# es.net
KiCad netlist of a schematic drawn in EAGLE
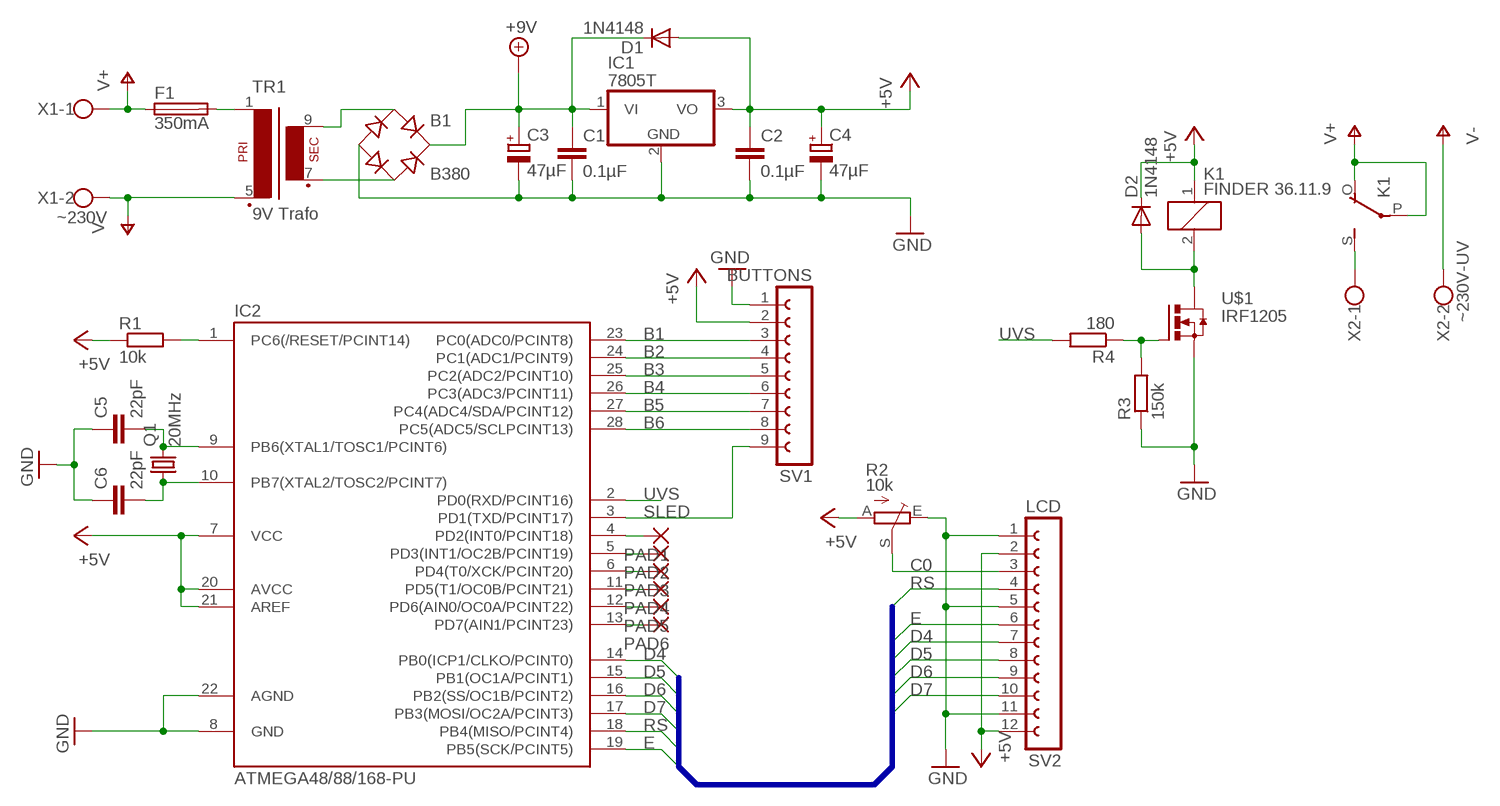
[diagram p0: schematic, sheet 1]

(export (version "E")
  (design (tool "Eeschema 10.0.6"))
  (components
    (comp (ref "B1")
      (value "B380")
      (footprint "eagle-import:RB1A")
      (libsource (lib "eagle-import") (part "RB1A"))
    )
    (comp (ref "C1")
      (value "0.1µF")
      (footprint "eagle-import:C025-024X044")
      (libsource (lib "eagle-import") (part "C-EU025-024X044"))
    )
    (comp (ref "C2")
      (value "0.1µF")
      (footprint "eagle-import:C025-024X044")
      (libsource (lib "eagle-import") (part "C-EU025-024X044"))
    )
    (comp (ref "C3")
      (value "47µF")
      (footprint "eagle-import:E2,5-5")
      (libsource (lib "eagle-import") (part "CPOL-EUE2.5-5"))
    )
    (comp (ref "C4")
      (value "47µF")
      (footprint "eagle-import:E2,5-5")
      (libsource (lib "eagle-import") (part "CPOL-EUE2.5-5"))
    )
    (comp (ref "C5")
      (value "22pF")
      (footprint "eagle-import:C050-024X044")
      (libsource (lib "eagle-import") (part "C-EU050-024X044"))
    )
    (comp (ref "C6")
      (value "22pF")
      (footprint "eagle-import:C050-024X044")
      (libsource (lib "eagle-import") (part "C-EU050-024X044"))
    )
    (comp (ref "D1")
      (value "1N4148")
      (footprint "eagle-import:DO35-7")
      (libsource (lib "eagle-import") (part "1N4148DO35-7"))
    )
    (comp (ref "D2")
      (value "1N4148")
      (footprint "eagle-import:DO35-7")
      (libsource (lib "eagle-import") (part "1N4148DO35-7"))
    )
    (comp (ref "F1")
      (value "350mA")
      (footprint "eagle-import:SHK20Q")
      (libsource (lib "eagle-import") (part "FUSESHK20Q"))
    )
    (comp (ref "IC1")
      (value "7805T")
      (footprint "eagle-import:TO220H")
      (libsource (lib "eagle-import") (part "78T05"))
    )
    (comp (ref "IC2")
      (value "ATMEGA48/88/168-PU")
      (footprint "eagle-import:DIL28-3")
      (libsource (lib "eagle-import") (part "ATMEGA48/88/168-PU"))
    )
    (comp (ref "K1")
      (value "FINDER 36.11.9")
      (footprint "eagle-import:G5LE")
      (libsource (lib "eagle-import") (part "G5LE"))
    )
    (comp (ref "PAD1")
      (value "1,6/0,8")
      (footprint "eagle-import:1,6_0,8")
      (libsource (lib "eagle-import") (part "1,6/0,8"))
    )
    (comp (ref "PAD2")
      (value "1,6/0,8")
      (footprint "eagle-import:1,6_0,8")
      (libsource (lib "eagle-import") (part "1,6/0,8"))
    )
    (comp (ref "PAD3")
      (value "1,6/0,8")
      (footprint "eagle-import:1,6_0,8")
      (libsource (lib "eagle-import") (part "1,6/0,8"))
    )
    (comp (ref "PAD4")
      (value "1,6/0,8")
      (footprint "eagle-import:1,6_0,8")
      (libsource (lib "eagle-import") (part "1,6/0,8"))
    )
    (comp (ref "PAD5")
      (value "1,6/0,8")
      (footprint "eagle-import:1,6_0,8")
      (libsource (lib "eagle-import") (part "1,6/0,8"))
    )
    (comp (ref "PAD6")
      (value "1,6/0,8")
      (footprint "eagle-import:1,6_0,8")
      (libsource (lib "eagle-import") (part "1,6/0,8"))
    )
    (comp (ref "Q1")
      (value "20MHz")
      (footprint "eagle-import:HC49_S")
      (libsource (lib "eagle-import") (part "CRYSTALHC49S"))
    )
    (comp (ref "R1")
      (value "10k")
      (footprint "eagle-import:0204_7")
      (libsource (lib "eagle-import") (part "R-EU_0204/7"))
    )
    (comp (ref "R2")
      (value "10k")
      (footprint "eagle-import:LI15")
      (libsource (lib "eagle-import") (part "TRIM_EU-LI15"))
    )
    (comp (ref "R3")
      (value "150k")
      (footprint "eagle-import:0204_7")
      (libsource (lib "eagle-import") (part "R-EU_0204/7"))
    )
    (comp (ref "R4")
      (value "180")
      (footprint "eagle-import:0204_7")
      (libsource (lib "eagle-import") (part "R-EU_0204/7"))
    )
    (comp (ref "SV1")
      (value "BUTTONS")
      (footprint "eagle-import:FE09")
      (libsource (lib "eagle-import") (part "FE09-1"))
    )
    (comp (ref "SV2")
      (value "LCD")
      (footprint "eagle-import:FE12")
      (libsource (lib "eagle-import") (part "FE12-1"))
    )
    (comp (ref "TR1")
      (value "9V Trafo")
      (footprint "eagle-import:EI42-1")
      (libsource (lib "eagle-import") (part "EI42-1"))
    )
    (comp (ref "U$1")
      (value "IRF1205")
      (footprint "eagle-import:I-PAK_TO251AA")
      (libsource (lib "eagle-import") (part "IRF1205"))
    )
    (comp (ref "X1")
      (value "~230V")
      (footprint "eagle-import:W237-2N")
      (libsource (lib "eagle-import") (part "W237-2N"))
    )
    (comp (ref "X2")
      (value "~230V-UV")
      (footprint "eagle-import:W237-2N")
      (libsource (lib "eagle-import") (part "W237-2N"))
    )
  )
  (nets
    (net (code "1") (name "+5V") (class "Default")
      (node (ref "C2") (pin "1") (pinfunction "1_1") (pintype "passive"))
      (node (ref "C4") (pin "+") (pinfunction "+_+") (pintype "passive"))
      (node (ref "D1") (pin "A") (pinfunction "A_A") (pintype "passive"))
      (node (ref "D2") (pin "C") (pinfunction "C_C") (pintype "passive"))
      (node (ref "IC1") (pin "3") (pinfunction "VO_3") (pintype "passive"))
      (node (ref "IC2") (pin "20") (pinfunction "AVCC_20") (pintype "passive"))
      (node (ref "IC2") (pin "21") (pinfunction "AREF_21") (pintype "passive"))
      (node (ref "IC2") (pin "7") (pinfunction "VCC_7") (pintype "power_in"))
      (node (ref "K1") (pin "1") (pinfunction "1_1") (pintype "passive"))
      (node (ref "R1") (pin "1") (pinfunction "1_1") (pintype "passive"))
      (node (ref "R2") (pin "A") (pinfunction "A_A") (pintype "passive"))
      (node (ref "SV1") (pin "2") (pinfunction "2_2") (pintype "passive"))
      (node (ref "SV2") (pin "12") (pinfunction "12_12") (pintype "passive"))
      (node (ref "SV2") (pin "2") (pinfunction "2_2") (pintype "passive"))
    )
    (net (code "2") (name "+9V") (class "Default")
      (node (ref "B1") (pin "+") (pinfunction "+_+") (pintype "passive"))
      (node (ref "C1") (pin "1") (pinfunction "1_1") (pintype "passive"))
      (node (ref "C3") (pin "+") (pinfunction "+_+") (pintype "passive"))
      (node (ref "D1") (pin "C") (pinfunction "C_C") (pintype "passive"))
      (node (ref "IC1") (pin "1") (pinfunction "VI_1") (pintype "input"))
    )
    (net (code "3") (name "/B1") (class "Default")
      (node (ref "IC2") (pin "23") (pinfunction "PC0(ADC0/PCINT8)_23") (pintype "bidirectional"))
      (node (ref "SV1") (pin "3") (pinfunction "3_3") (pintype "passive"))
    )
    (net (code "4") (name "/B2") (class "Default")
      (node (ref "IC2") (pin "24") (pinfunction "PC1(ADC1/PCINT9)_24") (pintype "bidirectional"))
      (node (ref "SV1") (pin "4") (pinfunction "4_4") (pintype "passive"))
    )
    (net (code "5") (name "/B3") (class "Default")
      (node (ref "IC2") (pin "25") (pinfunction "PC2(ADC2/PCINT10)_25") (pintype "bidirectional"))
      (node (ref "SV1") (pin "5") (pinfunction "5_5") (pintype "passive"))
    )
    (net (code "6") (name "/B4") (class "Default")
      (node (ref "IC2") (pin "26") (pinfunction "PC3(ADC3/PCINT11)_26") (pintype "bidirectional"))
      (node (ref "SV1") (pin "6") (pinfunction "6_6") (pintype "passive"))
    )
    (net (code "7") (name "/B5") (class "Default")
      (node (ref "IC2") (pin "27") (pinfunction "PC4(ADC4/SDA/PCINT12)_27") (pintype "bidirectional"))
      (node (ref "SV1") (pin "7") (pinfunction "7_7") (pintype "passive"))
    )
    (net (code "8") (name "/B6") (class "Default")
      (node (ref "IC2") (pin "28") (pinfunction "PC5(ADC5/SCLPCINT13)_28") (pintype "bidirectional"))
      (node (ref "SV1") (pin "8") (pinfunction "8_8") (pintype "passive"))
    )
    (net (code "9") (name "/C0") (class "Default")
      (node (ref "R2") (pin "S") (pinfunction "S_S") (pintype "passive"))
      (node (ref "SV2") (pin "3") (pinfunction "3_3") (pintype "passive"))
    )
    (net (code "10") (name "/D4") (class "Default")
      (node (ref "IC2") (pin "14") (pinfunction "PB0(ICP1/CLKO/PCINT0)_14") (pintype "bidirectional"))
      (node (ref "SV2") (pin "7") (pinfunction "7_7") (pintype "passive"))
    )
    (net (code "11") (name "/D5") (class "Default")
      (node (ref "IC2") (pin "15") (pinfunction "PB1(OC1A/PCINT1)_15") (pintype "bidirectional"))
      (node (ref "SV2") (pin "8") (pinfunction "8_8") (pintype "passive"))
    )
    (net (code "12") (name "/D6") (class "Default")
      (node (ref "IC2") (pin "16") (pinfunction "PB2(SS/OC1B/PCINT2)_16") (pintype "bidirectional"))
      (node (ref "SV2") (pin "9") (pinfunction "9_9") (pintype "passive"))
    )
    (net (code "13") (name "/D7") (class "Default")
      (node (ref "IC2") (pin "17") (pinfunction "PB3(MOSI/OC2A/PCINT3)_17") (pintype "bidirectional"))
      (node (ref "SV2") (pin "10") (pinfunction "10_10") (pintype "passive"))
    )
    (net (code "14") (name "/E") (class "Default")
      (node (ref "IC2") (pin "19") (pinfunction "PB5(SCK/PCINT5)_19") (pintype "bidirectional"))
      (node (ref "SV2") (pin "6") (pinfunction "6_6") (pintype "passive"))
    )
    (net (code "15") (name "/RS") (class "Default")
      (node (ref "IC2") (pin "18") (pinfunction "PB4(MISO/PCINT4)_18") (pintype "bidirectional"))
      (node (ref "SV2") (pin "4") (pinfunction "4_4") (pintype "passive"))
    )
    (net (code "16") (name "/SLED") (class "Default")
      (node (ref "IC2") (pin "3") (pinfunction "PD1(TXD/PCINT17)_3") (pintype "bidirectional"))
      (node (ref "SV1") (pin "9") (pinfunction "9_9") (pintype "passive"))
    )
    (net (code "17") (name "/UVS") (class "Default")
      (node (ref "IC2") (pin "2") (pinfunction "PD0(RXD/PCINT16)_2") (pintype "bidirectional"))
      (node (ref "R4") (pin "2") (pinfunction "2_2") (pintype "passive"))
    )
    (net (code "18") (name "GND") (class "Default")
      (node (ref "B1") (pin "-") (pinfunction "-_-") (pintype "passive"))
      (node (ref "C1") (pin "2") (pinfunction "2_2") (pintype "passive"))
      (node (ref "C2") (pin "2") (pinfunction "2_2") (pintype "passive"))
      (node (ref "C3") (pin "-") (pinfunction "-_-") (pintype "passive"))
      (node (ref "C4") (pin "-") (pinfunction "-_-") (pintype "passive"))
      (node (ref "C5") (pin "1") (pinfunction "1_1") (pintype "passive"))
      (node (ref "C6") (pin "1") (pinfunction "1_1") (pintype "passive"))
      (node (ref "IC1") (pin "2") (pinfunction "GND_2") (pintype "passive"))
      (node (ref "IC2") (pin "22") (pinfunction "AGND_22") (pintype "power_in"))
      (node (ref "IC2") (pin "8") (pinfunction "GND_8") (pintype "power_in"))
      (node (ref "R2") (pin "E") (pinfunction "E_E") (pintype "passive"))
      (node (ref "R3") (pin "1") (pinfunction "1_1") (pintype "passive"))
      (node (ref "SV1") (pin "1") (pinfunction "1_1") (pintype "passive"))
      (node (ref "SV2") (pin "1") (pinfunction "1_1") (pintype "passive"))
      (node (ref "SV2") (pin "11") (pinfunction "11_11") (pintype "passive"))
      (node (ref "SV2") (pin "5") (pinfunction "5_5") (pintype "passive"))
      (node (ref "U$1") (pin "3") (pinfunction "S_3") (pintype "passive"))
    )
    (net (code "19") (name "Net-(F1-2)") (class "Default")
      (node (ref "F1") (pin "2A") (pinfunction "2_2A") (pintype "passive"))
      (node (ref "TR1") (pin "1") (pinfunction "P1_1") (pintype "passive"))
    )
    (net (code "20") (name "Net-(IC2-PB6(XTAL1{slash}TOSC1{slash}PCINT6))") (class "Default")
      (node (ref "C5") (pin "2") (pinfunction "2_2") (pintype "passive"))
      (node (ref "IC2") (pin "9") (pinfunction "PB6(XTAL1/TOSC1/PCINT6)_9") (pintype "bidirectional"))
      (node (ref "Q1") (pin "2") (pinfunction "2_2") (pintype "passive"))
    )
    (net (code "21") (name "Net-(IC2-PB7(XTAL2{slash}TOSC2{slash}PCINT7))") (class "Default")
      (node (ref "C6") (pin "2") (pinfunction "2_2") (pintype "passive"))
      (node (ref "IC2") (pin "10") (pinfunction "PB7(XTAL2/TOSC2/PCINT7)_10") (pintype "bidirectional"))
      (node (ref "Q1") (pin "1") (pinfunction "1_1") (pintype "passive"))
    )
    (net (code "22") (name "Net-(IC2-PC6({slash}RESET{slash}PCINT14))") (class "Default")
      (node (ref "IC2") (pin "1") (pinfunction "PC6(/RESET/PCINT14)_1") (pintype "bidirectional"))
      (node (ref "R1") (pin "2") (pinfunction "2_2") (pintype "passive"))
    )
    (net (code "23") (name "Net-(IC2-PD2(INT0{slash}PCINT18))") (class "Default")
      (node (ref "IC2") (pin "4") (pinfunction "PD2(INT0/PCINT18)_4") (pintype "bidirectional"))
      (node (ref "PAD1") (pin "1") (pinfunction "P_1") (pintype "passive"))
    )
    (net (code "24") (name "Net-(IC2-PD3(INT1{slash}OC2B{slash}PCINT19))") (class "Default")
      (node (ref "IC2") (pin "5") (pinfunction "PD3(INT1/OC2B/PCINT19)_5") (pintype "bidirectional"))
      (node (ref "PAD2") (pin "1") (pinfunction "P_1") (pintype "passive"))
    )
    (net (code "25") (name "Net-(IC2-PD4(T0{slash}XCK{slash}PCINT20))") (class "Default")
      (node (ref "IC2") (pin "6") (pinfunction "PD4(T0/XCK/PCINT20)_6") (pintype "bidirectional"))
      (node (ref "PAD3") (pin "1") (pinfunction "P_1") (pintype "passive"))
    )
    (net (code "26") (name "Net-(IC2-PD5(T1{slash}OC0B{slash}PCINT21))") (class "Default")
      (node (ref "IC2") (pin "11") (pinfunction "PD5(T1/OC0B/PCINT21)_11") (pintype "bidirectional"))
      (node (ref "PAD4") (pin "1") (pinfunction "P_1") (pintype "passive"))
    )
    (net (code "27") (name "Net-(IC2-PD6(AIN0{slash}OC0A{slash}PCINT22))") (class "Default")
      (node (ref "IC2") (pin "12") (pinfunction "PD6(AIN0/OC0A/PCINT22)_12") (pintype "bidirectional"))
      (node (ref "PAD5") (pin "1") (pinfunction "P_1") (pintype "passive"))
    )
    (net (code "28") (name "Net-(IC2-PD7(AIN1{slash}PCINT23))") (class "Default")
      (node (ref "IC2") (pin "13") (pinfunction "PD7(AIN1/PCINT23)_13") (pintype "bidirectional"))
      (node (ref "PAD6") (pin "1") (pinfunction "P_1") (pintype "passive"))
    )
    (net (code "29") (name "Net-(TR1-S3)") (class "Default")
      (node (ref "B1") (pin "AC2") (pinfunction "AC2_AC2") (pintype "passive"))
      (node (ref "TR1") (pin "7") (pinfunction "S3_7") (pintype "passive"))
    )
    (net (code "30") (name "Net-(TR1-S4)") (class "Default")
      (node (ref "B1") (pin "AC1") (pinfunction "AC1_AC1") (pintype "passive"))
      (node (ref "TR1") (pin "9") (pinfunction "S4_9") (pintype "passive"))
    )
    (net (code "31") (name "Net-(U$1-D)") (class "Default")
      (node (ref "D2") (pin "A") (pinfunction "A_A") (pintype "passive"))
      (node (ref "K1") (pin "2") (pinfunction "2_2") (pintype "passive"))
      (node (ref "U$1") (pin "2") (pinfunction "D_2") (pintype "passive"))
    )
    (net (code "32") (name "Net-(U$1-G)") (class "Default")
      (node (ref "R3") (pin "2") (pinfunction "2_2") (pintype "passive"))
      (node (ref "R4") (pin "1") (pinfunction "1_1") (pintype "passive"))
      (node (ref "U$1") (pin "1") (pinfunction "G_1") (pintype "passive"))
    )
    (net (code "33") (name "Net-(X2A-KL)") (class "Default")
      (node (ref "K1") (pin "S") (pinfunction "S_S") (pintype "passive"))
      (node (ref "X2") (pin "1") (pinfunction "KL_1") (pintype "passive"))
    )
    (net (code "34") (name "V+") (class "Default")
      (node (ref "F1") (pin "1A") (pinfunction "1_1A") (pintype "passive"))
      (node (ref "K1") (pin "O") (pinfunction "O_O") (pintype "passive"))
      (node (ref "K1") (pin "P") (pinfunction "P_P") (pintype "passive"))
      (node (ref "X1") (pin "1") (pinfunction "KL_1") (pintype "passive"))
    )
    (net (code "35") (name "V-") (class "Default")
      (node (ref "TR1") (pin "5") (pinfunction "P2_5") (pintype "passive"))
      (node (ref "X1") (pin "2") (pinfunction "KL_2") (pintype "passive"))
      (node (ref "X2") (pin "2") (pinfunction "KL_2") (pintype "passive"))
    )
  )
)
